# HVcircuit.net
KiCad netlist of a schematic drawn in Altium Designer
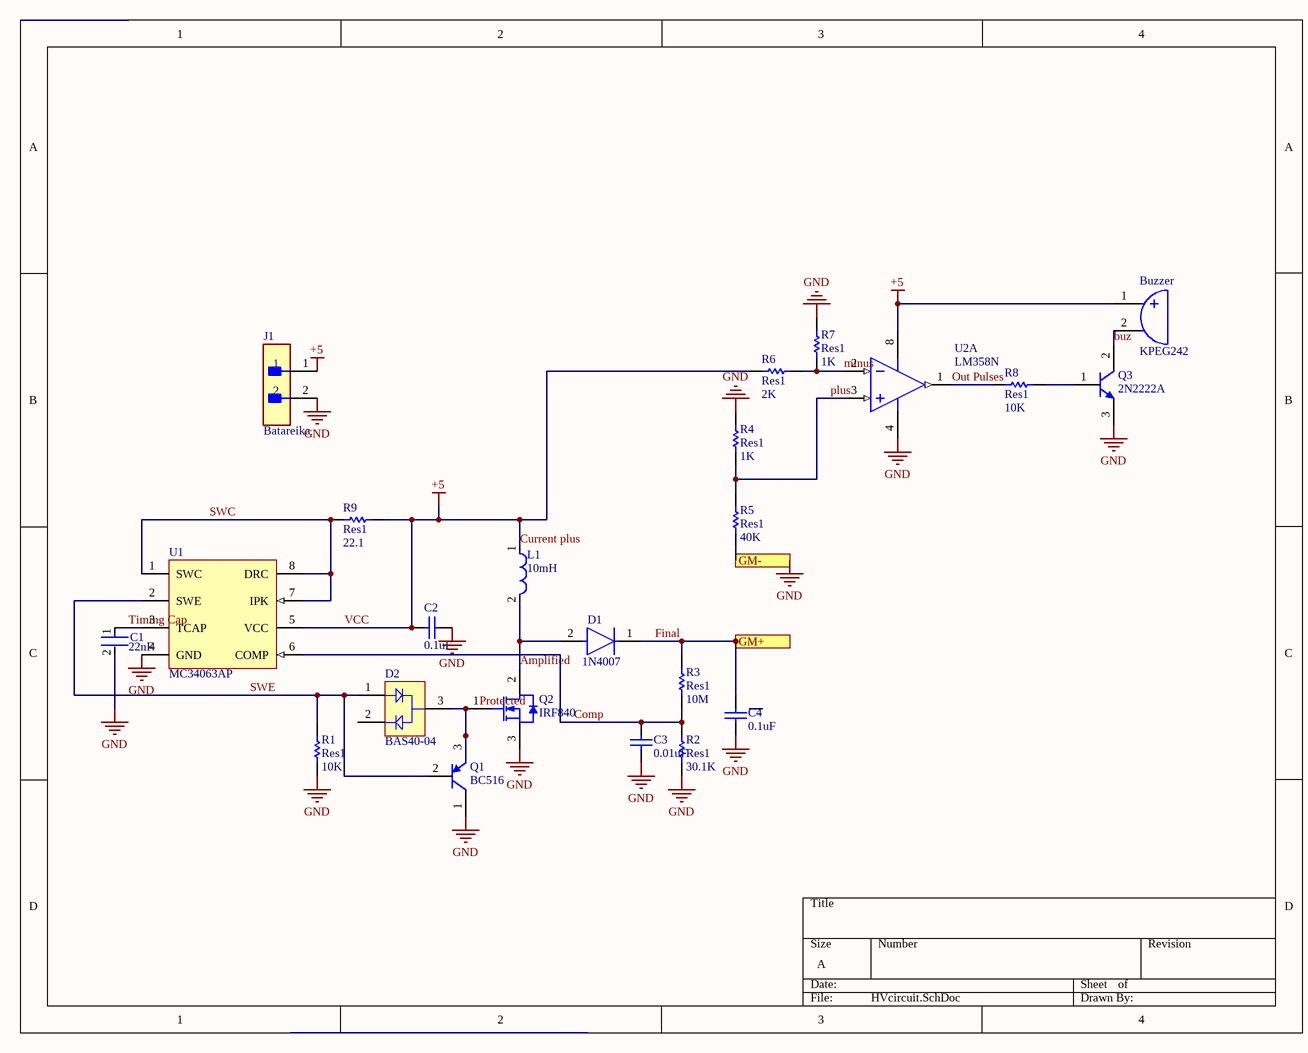
[diagram p0: HVcircuit.SchDoc]

(export (version "E")
  (design (tool "Eeschema 10.0.6"))
  (components
    (comp (ref "Buzzer")
      (value "KPEG242")
      (footprint "KINGS-KPEG242-2")
      (description "Piezo Indicator, 4100 Hz, 3 to 16 V, -20 to 70 degC, 2-Pin THD, RoHS")
      (fields (field (name "PARTNUMBER") "KPE-242") (field (name "MANUFACTURER") "KingstateElectronicsCorp."))
      (libsource (lib "Altium Content Vault") (part "KINGS-KPEG242-2"))
    )
    (comp (ref "C1")
      (value "22nF")
      (footprint "FP-RCE1K1-2_5-MFG")
      (description "Cap Ceramic Monolithic 22nF 50V 5% Thru-Hole Bulk")
      (fields (field (name "TOLERANCE") "5%"))
      (libsource (lib "Altium Content Vault") (part "02cd4be3c70576c341d710602a673aa"))
    )
    (comp (ref "C2")
      (value "0.1uF")
      (footprint "CAPR51-254-508X318X736")
      (libsource (lib "Altium Content Vault") (part "CAP-NP-2"))
    )
    (comp (ref "C3")
      (value "0.01uF")
      (footprint "KEMT-C315-THT-2")
      (description "Capacitor, Ceramic, 0.01 uF, +/- 10%, 100 V, X7R, -55 to 125 degC, 2-Pin THD, RoHS, Bulk")
      (libsource (lib "Altium Content Vault") (part "CAP-NP-2"))
    )
    (comp (ref "C4")
      (value "0.1uF")
      (footprint "CAPR51-254-508X318X736")
      (libsource (lib "Altium Content Vault") (part "CAP-NP-2"))
    )
    (comp (ref "D1")
      (value "1N4007")
      (footprint "FP-1N4007-MFG")
      (description "Rectifier diode 1000 V 1 A DO-41, ,")
      (fields
        (field (name "MANUFACTURER") "Diotec")
        (field (name "OCTOPART") "https://octopart.com/1n4007-diotec-4040411")
      )
      (libsource (lib "Altium Content Vault") (part "d7152d700b627762746794eb795d46e"))
    )
    (comp (ref "D2")
      (value "BAS40-04")
      (footprint "INF-SOT23_L")
      (description "Silicon Schottky Diode, -55 to 150 degC, SOT23, Reel, Green")
      (fields (field (name "MANUFACTURER") "Infineon"))
      (libsource (lib "Altium Content Vault") (part "INF-D_A1K2C3-3"))
    )
    (comp (ref "J1")
      (value "Batareika")
      (footprint "FP-350428-1-MFG")
      (description "CONN HEADER VERT 2POS 6.35MM")
      (fields
        (field (name "OCTOPART") "https://octopart.com/350428-1-te+connectivity-46505355")
        (field (name "MANUFACTURER") "TE Connectivity")
      )
      (libsource (lib "Altium Content Vault") (part "3bc925449376181038e59eaffc5286c"))
    )
    (comp (ref "L1")
      (value "10mH")
      (footprint "FP-LQH55DN_03-MFG")
      (description "Wire Wound Ferrite Inductor for Power Lines 10000μH ±20% 140Ω  0.05A 2220")
      (fields (field (name "TOLERANCE") "20%"))
      (libsource (lib "Altium Content Vault") (part "725321dda6339637d4d059423bc1c3c"))
    )
    (comp (ref "Q1")
      (value "BC516")
      (footprint "ONSC-TO-92-3-29-11")
      (description "Amplifier Transistor, PNP Silicon, 3-Pin TO-92, Pb-Free, Bulk Box")
      (fields (field (name "MANUFACTURER") "On Semiconductor") (field (name "PARTNUMBER") "BC557CG"))
      (libsource (lib "Altium Content Vault") (part "ONSC-PNP-C1B2E3-3"))
    )
    (comp (ref "Q2")
      (value "IRF840")
      (footprint "VISH-TO-220AB-3")
      (description "Power MOSFET, 500 V, -55 to 150 degC, 3-Pin FM, RoHS, Tape and Reel")
      (fields (field (name "MANUFACTURER") "Vishay"))
      (libsource (lib "Altium Content Vault") (part "NXP-NMOS-GDS-3"))
    )
    (comp (ref "Q3")
      (value "2N2222A")
      (footprint "STM-TO-18-3")
      (description "High Speed Switch, 0.6 A IC, -65 to 175 degC, 3-Pin TO-18, RoHS, Bulk")
      (fields (field (name "MANUFACTURER") "STMicroelectronics"))
      (libsource (lib "Altium Content Vault") (part "NPN_B1C2E3-3"))
    )
    (comp (ref "R1")
      (value "Res1")
      (footprint "AXIAL-0.3")
      (description "Resistor")
      (fields (field (name "ALTIUM_VALUE") "10K") (field (name "PUBLISHER") "Altium Limited"))
      (libsource (lib "Miscellaneous Devices") (part "Res1"))
    )
    (comp (ref "R2")
      (value "Res1")
      (footprint "AXIAL-0.3")
      (description "Resistor")
      (fields (field (name "ALTIUM_VALUE") "30.1K") (field (name "PUBLISHER") "Altium Limited"))
      (libsource (lib "Miscellaneous Devices") (part "Res1"))
    )
    (comp (ref "R3")
      (value "Res1")
      (footprint "AXIAL-0.3")
      (description "Resistor")
      (fields (field (name "ALTIUM_VALUE") "10M") (field (name "PUBLISHER") "Altium Limited"))
      (libsource (lib "Miscellaneous Devices") (part "Res1"))
    )
    (comp (ref "R4")
      (value "Res1")
      (footprint "AXIAL-0.3")
      (description "Resistor")
      (fields (field (name "ALTIUM_VALUE") "1K") (field (name "PUBLISHER") "Altium Limited"))
      (libsource (lib "Miscellaneous Devices") (part "Res1"))
    )
    (comp (ref "R5")
      (value "Res1")
      (footprint "AXIAL-0.3")
      (description "Resistor")
      (fields (field (name "ALTIUM_VALUE") "40K") (field (name "PUBLISHER") "Altium Limited"))
      (libsource (lib "Miscellaneous Devices") (part "Res1"))
    )
    (comp (ref "R6")
      (value "Res1")
      (footprint "AXIAL-0.3")
      (description "Resistor")
      (fields (field (name "ALTIUM_VALUE") "2K") (field (name "PUBLISHER") "Altium Limited"))
      (libsource (lib "Miscellaneous Devices") (part "Res1"))
    )
    (comp (ref "R7")
      (value "Res1")
      (footprint "AXIAL-0.3")
      (description "Resistor")
      (fields (field (name "ALTIUM_VALUE") "1K") (field (name "PUBLISHER") "Altium Limited"))
      (libsource (lib "Miscellaneous Devices") (part "Res1"))
    )
    (comp (ref "R8")
      (value "Res1")
      (footprint "AXIAL-0.3")
      (description "Resistor")
      (fields (field (name "ALTIUM_VALUE") "10K") (field (name "PUBLISHER") "Altium Limited"))
      (libsource (lib "Miscellaneous Devices") (part "Res1"))
    )
    (comp (ref "R9")
      (value "Res1")
      (footprint "AXIAL-0.3")
      (description "Resistor")
      (fields (field (name "ALTIUM_VALUE") "22.1") (field (name "PUBLISHER") "Altium Limited"))
      (libsource (lib "Miscellaneous Devices") (part "Res1"))
    )
    (comp (ref "U1")
      (value "MC34063AP")
      (footprint "P0008A")
      (fields (field (name "MANUFACTURER") "Texas Instruments"))
      (libsource (lib "Altium Content Vault") (part "TI-MC34063AP8"))
    )
    (comp (ref "U2")
      (value "LM358N")
      (footprint "ONSC-PDIP-8-626-05_M")
      (description "Single Supply Dual Operational Amplifier, 3 to 32 V, 0 to 70 degC, 8-Pin PDIP, Tube")
      (fields (field (name "MANUFACTURER") "On Semiconductor"))
      (libsource (lib "Altium Content Vault") (part "ONSC-LM358_NCV2904-8"))
    )
  )
  (nets
    (net (code "1") (name "+5") (class "Default")
      (node (ref "Buzzer") (pin "1") (pinfunction "1_1") (pintype "passive"))
      (node (ref "C2") (pin "1") (pinfunction "1_1") (pintype "passive"))
      (node (ref "J1") (pin "1") (pinfunction "1_1") (pintype "passive"))
      (node (ref "L1") (pin "1") (pinfunction "1_1") (pintype "passive"))
      (node (ref "R6") (pin "1") (pinfunction "1_1") (pintype "passive"))
      (node (ref "R9") (pin "1") (pinfunction "1_1") (pintype "passive"))
      (node (ref "U1") (pin "5") (pinfunction "VCC_5") (pintype "power_in"))
      (node (ref "U2") (pin "8") (pinfunction "VCC_8") (pintype "power_in"))
    )
    (net (code "2") (name "/Amplified") (class "Default")
      (node (ref "D1") (pin "2") (pinfunction "A_2") (pintype "passive"))
      (node (ref "L1") (pin "2") (pinfunction "2_2") (pintype "passive"))
      (node (ref "Q2") (pin "2") (pinfunction "D_2") (pintype "passive"))
    )
    (net (code "3") (name "/Comp") (class "Default")
      (node (ref "C3") (pin "1") (pinfunction "1_1") (pintype "passive"))
      (node (ref "R2") (pin "2") (pinfunction "2_2") (pintype "passive"))
      (node (ref "R3") (pin "1") (pinfunction "1_1") (pintype "passive"))
      (node (ref "U1") (pin "6") (pinfunction "COMP_6") (pintype "input"))
    )
    (net (code "4") (name "/Final") (class "Default")
      (node (ref "C4") (pin "2") (pinfunction "2_2") (pintype "passive"))
      (node (ref "D1") (pin "1") (pinfunction "C_1") (pintype "passive"))
      (node (ref "R3") (pin "2") (pinfunction "2_2") (pintype "passive"))
    )
    (net (code "5") (name "/Out Pulses") (class "Default")
      (node (ref "R8") (pin "1") (pinfunction "1_1") (pintype "passive"))
      (node (ref "U2") (pin "1") (pinfunction "OUTA_1") (pintype "output"))
    )
    (net (code "7") (name "/SWC") (class "Default")
      (node (ref "R9") (pin "2") (pinfunction "2_2") (pintype "passive"))
      (node (ref "U1") (pin "1") (pinfunction "SWC_1") (pintype "open_collector"))
      (node (ref "U1") (pin "7") (pinfunction "IPK_7") (pintype "input"))
      (node (ref "U1") (pin "8") (pinfunction "DRC_8") (pintype "open_collector"))
    )
    (net (code "8") (name "/SWE") (class "Default")
      (node (ref "D2") (pin "1") (pinfunction "A1_1") (pintype "passive"))
      (node (ref "Q1") (pin "2") (pinfunction "B_2") (pintype "passive"))
      (node (ref "R1") (pin "2") (pinfunction "2_2") (pintype "passive"))
      (node (ref "U1") (pin "2") (pinfunction "SWE_2") (pintype "open_emitter"))
    )
    (net (code "9") (name "/Timing Cap") (class "Default")
      (node (ref "C1") (pin "1") (pinfunction "1_1") (pintype "passive"))
      (node (ref "U1") (pin "3") (pinfunction "TCAP_3") (pintype "passive"))
    )
    (net (code "10") (name "/buz") (class "Default")
      (node (ref "Buzzer") (pin "2") (pinfunction "2_2") (pintype "passive"))
      (node (ref "Q3") (pin "2") (pinfunction "C_2") (pintype "passive"))
    )
    (net (code "11") (name "/minus") (class "Default")
      (node (ref "R6") (pin "2") (pinfunction "2_2") (pintype "passive"))
      (node (ref "R7") (pin "1") (pinfunction "1_1") (pintype "passive"))
      (node (ref "U2") (pin "2") (pinfunction "INA-_2") (pintype "input"))
    )
    (net (code "12") (name "/plus") (class "Default")
      (node (ref "R4") (pin "2") (pinfunction "2_2") (pintype "passive"))
      (node (ref "R5") (pin "2") (pinfunction "2_2") (pintype "passive"))
      (node (ref "U2") (pin "3") (pinfunction "INA+_3") (pintype "input"))
    )
    (net (code "13") (name "GND") (class "Default")
      (node (ref "C1") (pin "2") (pinfunction "2_2") (pintype "passive"))
      (node (ref "C2") (pin "2") (pinfunction "2_2") (pintype "passive"))
      (node (ref "C3") (pin "2") (pinfunction "2_2") (pintype "passive"))
      (node (ref "C4") (pin "1") (pinfunction "1_1") (pintype "passive"))
      (node (ref "J1") (pin "2") (pinfunction "2_2") (pintype "passive"))
      (node (ref "Q1") (pin "1") (pinfunction "C_1") (pintype "passive"))
      (node (ref "Q2") (pin "3") (pinfunction "S_3") (pintype "passive"))
      (node (ref "Q3") (pin "3") (pinfunction "E_3") (pintype "passive"))
      (node (ref "R1") (pin "1") (pinfunction "1_1") (pintype "passive"))
      (node (ref "R2") (pin "1") (pinfunction "1_1") (pintype "passive"))
      (node (ref "R4") (pin "1") (pinfunction "1_1") (pintype "passive"))
      (node (ref "R5") (pin "1") (pinfunction "1_1") (pintype "passive"))
      (node (ref "R7") (pin "2") (pinfunction "2_2") (pintype "passive"))
      (node (ref "U1") (pin "4") (pinfunction "GND_4") (pintype "power_in"))
      (node (ref "U2") (pin "4") (pinfunction "VEE/GND_4") (pintype "power_in"))
    )
    (net (code "14") (name "Net-(D2-C)") (class "Default")
      (node (ref "D2") (pin "3") (pinfunction "C_3") (pintype "passive"))
      (node (ref "Q1") (pin "3") (pinfunction "E_3") (pintype "passive"))
      (node (ref "Q2") (pin "1") (pinfunction "G_1") (pintype "passive"))
    )
    (net (code "15") (name "Net-(Q3-B)") (class "Default")
      (node (ref "Q3") (pin "1") (pinfunction "B_1") (pintype "passive"))
      (node (ref "R8") (pin "2") (pinfunction "2_2") (pintype "passive"))
    )
    (net (code "16") (name "unconnected-(D2-K2-Pad2)") (class "Default")
      (node (ref "D2") (pin "2") (pinfunction "K2_2") (pintype "passive"))
    )
  )
)
